# Voltage_monitor.net
KiCad netlist of a schematic drawn in EAGLE
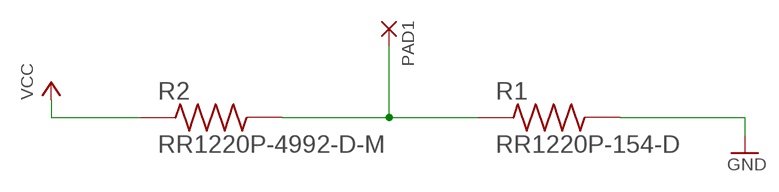
[diagram p0: schematic, sheet 1]

(export (version "E")
  (design (tool "Eeschema 10.0.6"))
  (components
    (comp (ref "PAD1")
      (value "SMD2")
      (footprint "eagle-import:SMD1,27-2,54")
      (libsource (lib "eagle-import") (part "SMD2"))
    )
    (comp (ref "R1")
      (value "RR1220P-154-D")
      (footprint "eagle-import:RESC2012X50N")
      (libsource (lib "eagle-import") (part "RR1220P-154-D"))
    )
    (comp (ref "R2")
      (value "RR1220P-4992-D-M")
      (footprint "eagle-import:RESC2012X50N")
      (libsource (lib "eagle-import") (part "RR1220P-4992-D-M"))
    )
  )
  (nets
    (net (code "1") (name "GND") (class "Default")
      (node (ref "R1") (pin "2") (pinfunction "2_2") (pintype "passive"))
    )
    (net (code "2") (name "Net-(PAD1-P)") (class "Default")
      (node (ref "PAD1") (pin "1") (pinfunction "P_1") (pintype "passive"))
      (node (ref "R1") (pin "1") (pinfunction "1_1") (pintype "passive"))
      (node (ref "R2") (pin "2") (pinfunction "2_2") (pintype "passive"))
    )
    (net (code "3") (name "VCC") (class "Default")
      (node (ref "R2") (pin "1") (pinfunction "1_1") (pintype "passive"))
    )
  )
)
